# NodoWifi_PER_R00.net
KiCad netlist of a schematic drawn in Altium Designer
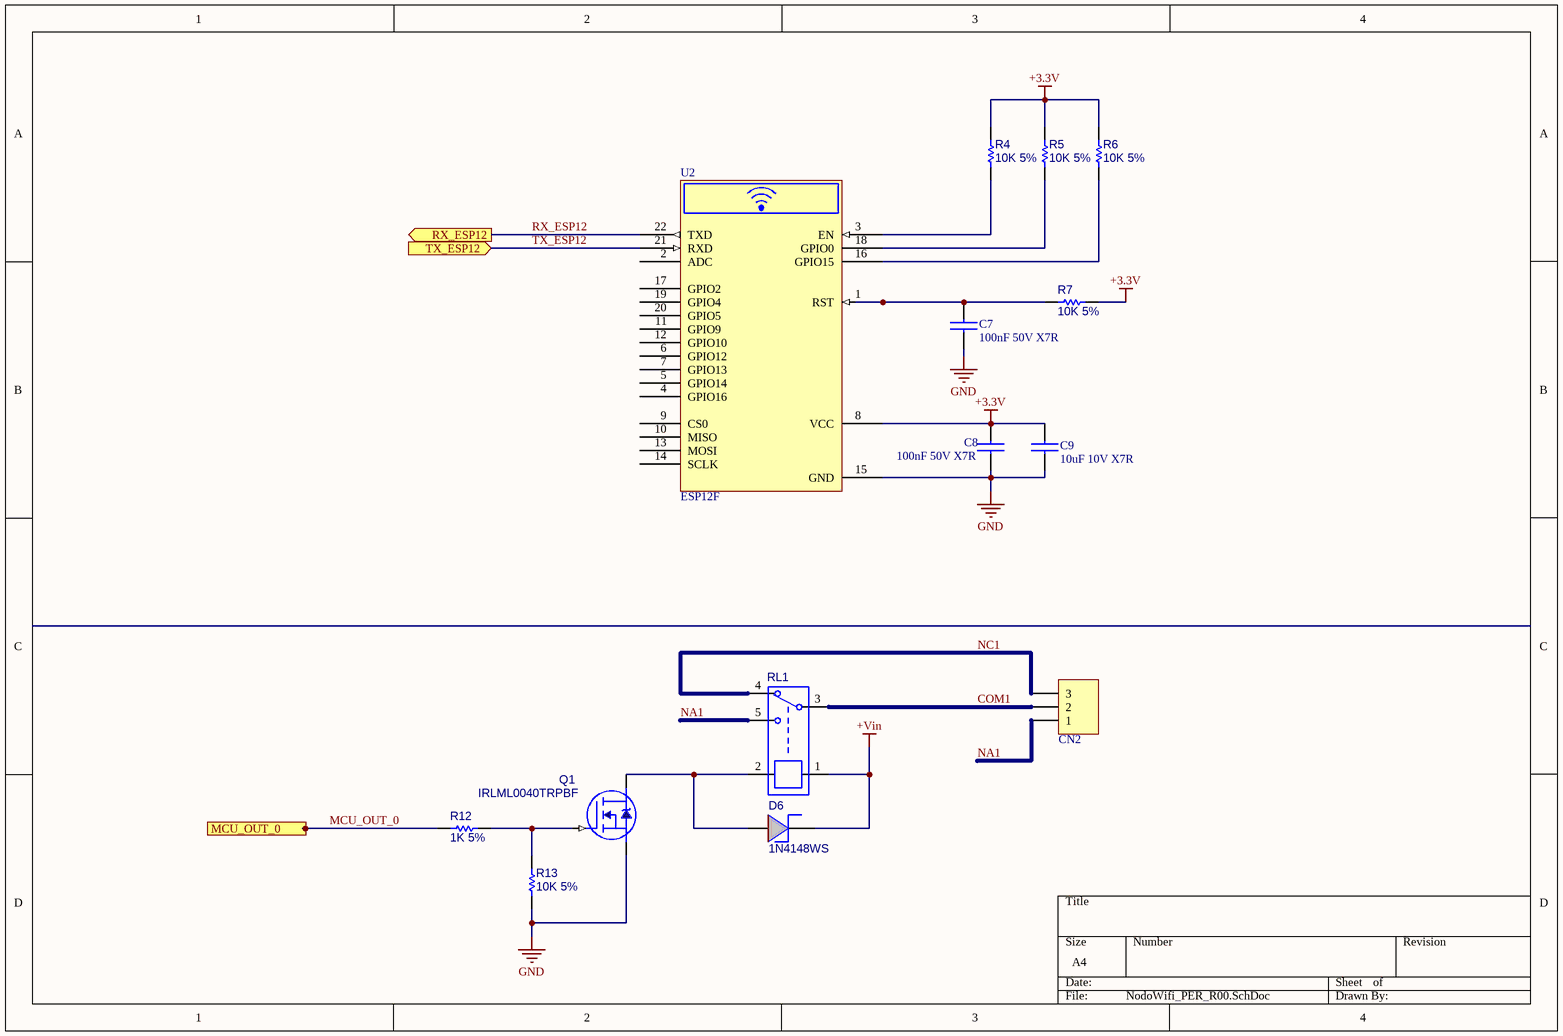
[diagram p0: NodoWifi_PER_R00.SchDoc]

(export (version "E")
  (design (tool "Eeschema 10.0.6"))
  (components
    (comp (ref "C7")
      (value "100nF 50V X7R")
      (footprint "C_0805")
      (description "Ceramic Capacitor")
      (libsource (lib "NodoWifi_R00") (part "Ceramic Capacitor"))
    )
    (comp (ref "C8")
      (value "100nF 50V X7R")
      (footprint "C_0805")
      (description "Ceramic Capacitor")
      (libsource (lib "NodoWifi_R00") (part "Ceramic Capacitor"))
    )
    (comp (ref "C9")
      (value "10uF 10V X7R")
      (footprint "C_0805")
      (description "Ceramic Capacitor")
      (libsource (lib "NodoWifi_R00") (part "Ceramic Capacitor"))
    )
    (comp (ref "CN2")
      (value "Bornera 3 Vias Pitch 5mm")
      (footprint "TerminalBlock_1x3_P5mm")
      (description "Connector Generic 3 Vias")
      (libsource (lib "NodoWifi_R00") (part "CONN_03P"))
    )
    (comp (ref "D6")
      (value "1N4148WS")
      (footprint "SOD_323")
      (description "Diode Shottky")
      (libsource (lib "NodoWifi_R00") (part "DIODO_SH"))
    )
    (comp (ref "Q1")
      (value "IRLML0040TRPBF")
      (footprint "SOT_23")
      (description "Mosfet N-Ch")
      (libsource (lib "NodoWifi_R00") (part "N_MOSFET_SOT23"))
    )
    (comp (ref "R4")
      (value "10K 5%")
      (footprint "R_0805")
      (description "Resistor")
      (libsource (lib "NodoWifi_R00") (part "Res1"))
    )
    (comp (ref "R5")
      (value "10K 5%")
      (footprint "R_0805")
      (description "Resistor")
      (libsource (lib "NodoWifi_R00") (part "Res1"))
    )
    (comp (ref "R6")
      (value "10K 5%")
      (footprint "R_0805")
      (description "Resistor")
      (libsource (lib "NodoWifi_R00") (part "Res1"))
    )
    (comp (ref "R7")
      (value "10K 5%")
      (footprint "R_0805")
      (description "Resistor")
      (libsource (lib "NodoWifi_R00") (part "Res1"))
    )
    (comp (ref "R12")
      (value "1K 5%")
      (footprint "R_0805")
      (description "Resistor")
      (libsource (lib "NodoWifi_R00") (part "Res1"))
    )
    (comp (ref "R13")
      (value "10K 5%")
      (footprint "R_0805")
      (description "Resistor")
      (libsource (lib "NodoWifi_R00") (part "Res1"))
    )
    (comp (ref "RL1")
      (value "SRD-24VDC-SLC")
      (footprint "943-1C")
      (description "Relay SPDT")
      (libsource (lib "NodoWifi_R00") (part "RELAY SPDT"))
    )
    (comp (ref "U2")
      (value "ESP12F")
      (footprint "ESP12F")
      (description "Wifi Module")
      (libsource (lib "NodoWifi_R00") (part "ESP12F Wifi Module"))
    )
  )
  (nets
    (net (code "1") (name "+3.3V") (class "Default")
      (node (ref "C8") (pin "1") (pinfunction "1_1") (pintype "passive"))
      (node (ref "C9") (pin "1") (pinfunction "1_1") (pintype "passive"))
      (node (ref "R4") (pin "2") (pinfunction "2_2") (pintype "passive"))
      (node (ref "R5") (pin "2") (pinfunction "2_2") (pintype "passive"))
      (node (ref "R6") (pin "2") (pinfunction "2_2") (pintype "passive"))
      (node (ref "R7") (pin "1") (pinfunction "1_1") (pintype "passive"))
      (node (ref "U2") (pin "8") (pinfunction "VCC_8") (pintype "power_in"))
    )
    (net (code "2") (name "+Vin") (class "Default")
      (node (ref "D6") (pin "2") (pinfunction "K_2") (pintype "passive"))
      (node (ref "RL1") (pin "1") (pinfunction "1_1") (pintype "passive"))
    )
    (net (code "3") (name "/COM1") (class "Default")
      (node (ref "CN2") (pin "2") (pinfunction "2_2") (pintype "passive"))
      (node (ref "RL1") (pin "3") (pinfunction "3_3") (pintype "passive"))
    )
    (net (code "4") (name "/MCU_OUT_0") (class "Default")
      (node (ref "R12") (pin "2") (pinfunction "2_2") (pintype "passive"))
    )
    (net (code "5") (name "/NA1") (class "Default")
      (node (ref "CN2") (pin "1") (pinfunction "1_1") (pintype "passive"))
      (node (ref "RL1") (pin "5") (pinfunction "5_5") (pintype "passive"))
    )
    (net (code "6") (name "/NC1") (class "Default")
      (node (ref "CN2") (pin "3") (pinfunction "3_3") (pintype "passive"))
      (node (ref "RL1") (pin "4") (pinfunction "4_4") (pintype "passive"))
    )
    (net (code "7") (name "/RX_ESP12") (class "Default")
      (node (ref "U2") (pin "22") (pinfunction "TXD_22") (pintype "output"))
    )
    (net (code "8") (name "/TX_ESP12") (class "Default")
      (node (ref "U2") (pin "21") (pinfunction "RXD_21") (pintype "input"))
    )
    (net (code "9") (name "GND") (class "Default")
      (node (ref "C7") (pin "2") (pinfunction "2_2") (pintype "passive"))
      (node (ref "C8") (pin "2") (pinfunction "2_2") (pintype "passive"))
      (node (ref "C9") (pin "2") (pinfunction "2_2") (pintype "passive"))
      (node (ref "Q1") (pin "2") (pinfunction "SOURCE_2") (pintype "passive"))
      (node (ref "R13") (pin "1") (pinfunction "1_1") (pintype "passive"))
      (node (ref "U2") (pin "15") (pinfunction "GND_15") (pintype "power_in"))
    )
    (net (code "10") (name "Net-(D6-A)") (class "Default")
      (node (ref "D6") (pin "1") (pinfunction "A_1") (pintype "passive"))
      (node (ref "Q1") (pin "3") (pinfunction "DRAIN_3") (pintype "passive"))
      (node (ref "RL1") (pin "2") (pinfunction "2_2") (pintype "passive"))
    )
    (net (code "11") (name "Net-(Q1-GATE)") (class "Default")
      (node (ref "Q1") (pin "1") (pinfunction "GATE_1") (pintype "input"))
      (node (ref "R12") (pin "1") (pinfunction "1_1") (pintype "passive"))
      (node (ref "R13") (pin "2") (pinfunction "2_2") (pintype "passive"))
    )
    (net (code "12") (name "Net-(U2-EN)") (class "Default")
      (node (ref "R4") (pin "1") (pinfunction "1_1") (pintype "passive"))
      (node (ref "U2") (pin "3") (pinfunction "EN_3") (pintype "input"))
    )
    (net (code "13") (name "Net-(U2-GPIO0)") (class "Default")
      (node (ref "R5") (pin "1") (pinfunction "1_1") (pintype "passive"))
      (node (ref "U2") (pin "18") (pinfunction "GPIO0_18") (pintype "passive"))
    )
    (net (code "14") (name "Net-(U2-GPIO15)") (class "Default")
      (node (ref "R6") (pin "1") (pinfunction "1_1") (pintype "passive"))
      (node (ref "U2") (pin "16") (pinfunction "GPIO15_16") (pintype "passive"))
    )
    (net (code "15") (name "Net-(U2-RST)") (class "Default")
      (node (ref "C7") (pin "1") (pinfunction "1_1") (pintype "passive"))
      (node (ref "R7") (pin "2") (pinfunction "2_2") (pintype "passive"))
      (node (ref "U2") (pin "1") (pinfunction "RST_1") (pintype "input"))
    )
    (net (code "16") (name "unconnected-(U2-ADC-Pad2)") (class "Default")
      (node (ref "U2") (pin "2") (pinfunction "ADC_2") (pintype "passive"))
    )
    (net (code "17") (name "unconnected-(U2-CS0-Pad9)") (class "Default")
      (node (ref "U2") (pin "9") (pinfunction "CS0_9") (pintype "passive"))
    )
    (net (code "18") (name "unconnected-(U2-GPIO2-Pad17)") (class "Default")
      (node (ref "U2") (pin "17") (pinfunction "GPIO2_17") (pintype "passive"))
    )
    (net (code "19") (name "unconnected-(U2-GPIO4-Pad19)") (class "Default")
      (node (ref "U2") (pin "19") (pinfunction "GPIO4_19") (pintype "passive"))
    )
    (net (code "20") (name "unconnected-(U2-GPIO5-Pad20)") (class "Default")
      (node (ref "U2") (pin "20") (pinfunction "GPIO5_20") (pintype "passive"))
    )
    (net (code "21") (name "unconnected-(U2-GPIO9-Pad11)") (class "Default")
      (node (ref "U2") (pin "11") (pinfunction "GPIO9_11") (pintype "passive"))
    )
    (net (code "22") (name "unconnected-(U2-GPIO10-Pad12)") (class "Default")
      (node (ref "U2") (pin "12") (pinfunction "GPIO10_12") (pintype "passive"))
    )
    (net (code "23") (name "unconnected-(U2-GPIO12-Pad6)") (class "Default")
      (node (ref "U2") (pin "6") (pinfunction "GPIO12_6") (pintype "passive"))
    )
    (net (code "24") (name "unconnected-(U2-GPIO13-Pad7)") (class "Default")
      (node (ref "U2") (pin "7") (pinfunction "GPIO13_7") (pintype "passive"))
    )
    (net (code "25") (name "unconnected-(U2-GPIO14-Pad5)") (class "Default")
      (node (ref "U2") (pin "5") (pinfunction "GPIO14_5") (pintype "passive"))
    )
    (net (code "26") (name "unconnected-(U2-GPIO16-Pad4)") (class "Default")
      (node (ref "U2") (pin "4") (pinfunction "GPIO16_4") (pintype "passive"))
    )
    (net (code "27") (name "unconnected-(U2-MISO-Pad10)") (class "Default")
      (node (ref "U2") (pin "10") (pinfunction "MISO_10") (pintype "passive"))
    )
    (net (code "28") (name "unconnected-(U2-MOSI-Pad13)") (class "Default")
      (node (ref "U2") (pin "13") (pinfunction "MOSI_13") (pintype "passive"))
    )
    (net (code "29") (name "unconnected-(U2-SCLK-Pad14)") (class "Default")
      (node (ref "U2") (pin "14") (pinfunction "SCLK_14") (pintype "passive"))
    )
  )
)
